# STORAGE.net
KiCad netlist of a schematic drawn in Altium Designer
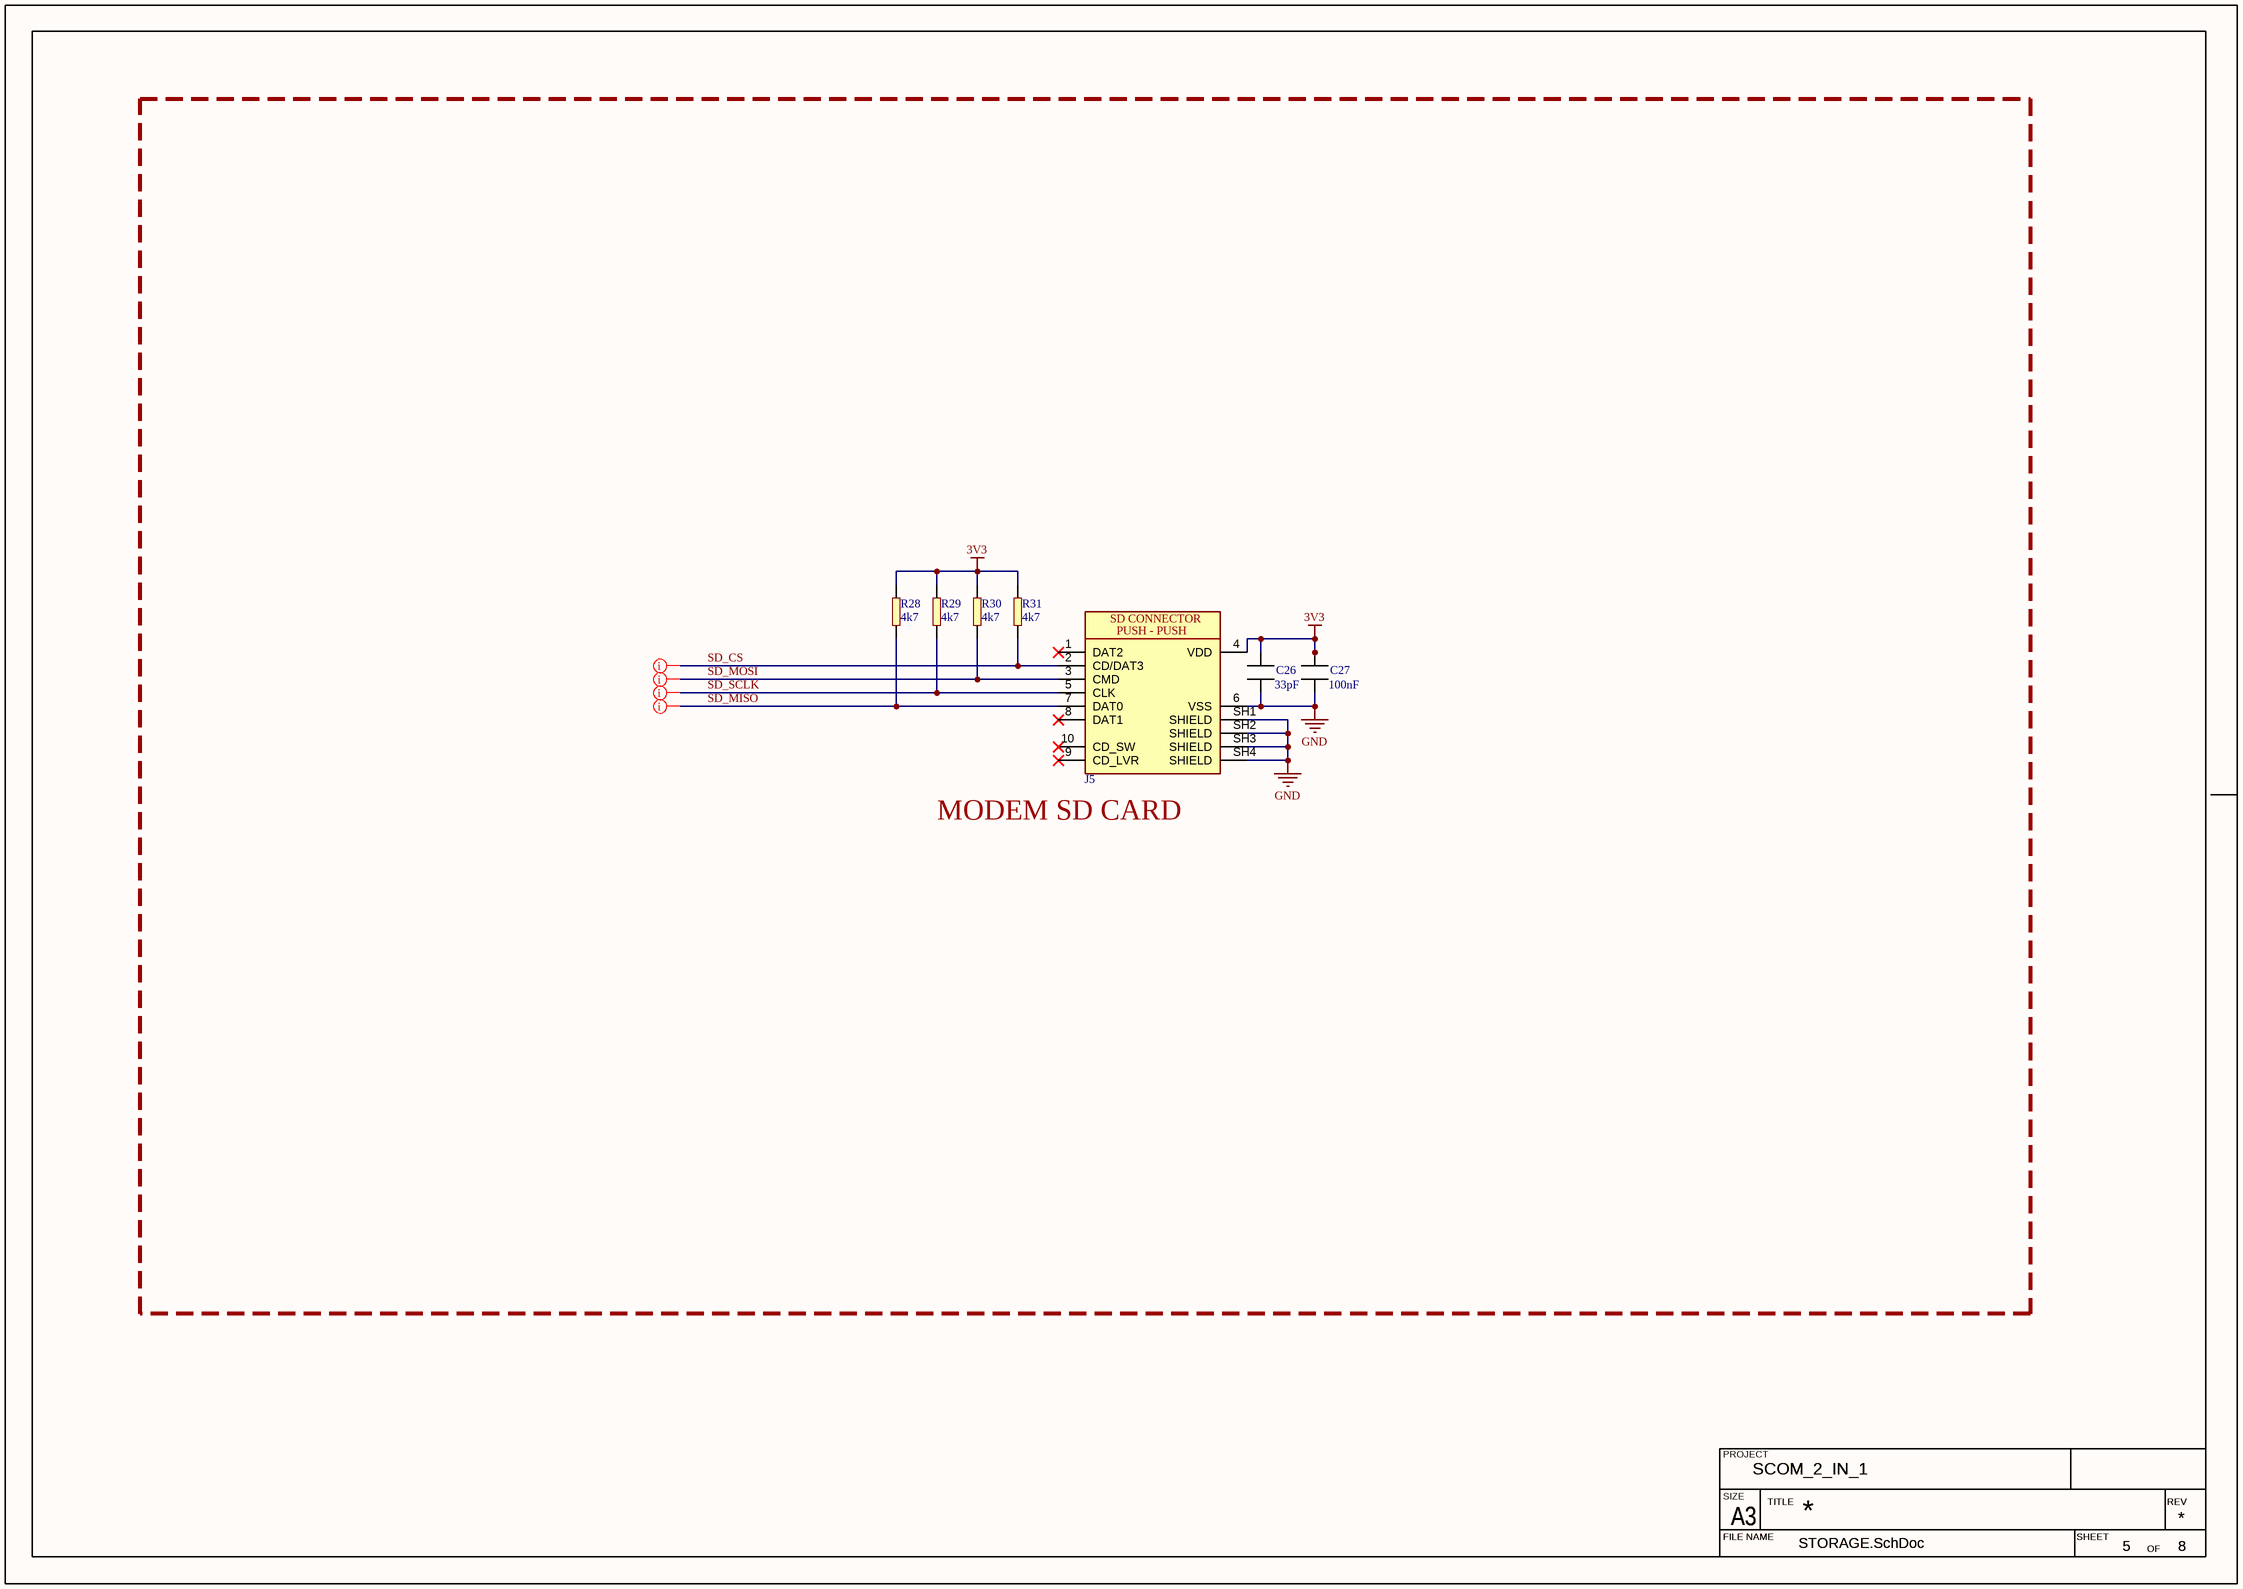
[diagram p0: STORAGE.SchDoc]

(export (version "E")
  (design (tool "Eeschema 10.0.6"))
  (components
    (comp (ref "C26")
      (value "33pF")
      (footprint "CAPC2012X13L")
      (description "Chip Capacitor, 2-Leads, Body 2.00x1.25mm, IPC High Density")
      (fields (field (name "Comment") "MLCC_0805"))
      (libsource (lib "Capacitor") (part "MLCC_0805"))
    )
    (comp (ref "C27")
      (value "100nF")
      (footprint "CAPC2012X13L")
      (description "Chip Capacitor, 2-Leads, Body 2.00x1.25mm, IPC High Density")
      (fields (field (name "Comment") "MLCC_0805"))
      (libsource (lib "Capacitor") (part "MLCC_0805"))
    )
    (comp (ref "J5")
      (value "5033981892")
      (footprint "5033981892")
      (description "9 (8 + 1) Position Card Connector Secure Digital - microSD™ Surface Mount, Right Angle Gold")
      (libsource (lib "Connectors") (part "5033981892"))
    )
    (comp (ref "R28")
      (value "4k7")
      (footprint "RES_0603")
      (description "RES_0603")
      (fields (field (name "Comment") "ERP_101-1"))
      (libsource (lib "Resistor") (part "RES_0603"))
    )
    (comp (ref "R29")
      (value "4k7")
      (footprint "RES_0603")
      (description "RES_0603")
      (fields (field (name "Comment") "ERP_101-1"))
      (libsource (lib "Resistor") (part "RES_0603"))
    )
    (comp (ref "R30")
      (value "4k7")
      (footprint "RES_0603")
      (description "RES_0603")
      (fields (field (name "Comment") "ERP_101-1"))
      (libsource (lib "Resistor") (part "RES_0603"))
    )
    (comp (ref "R31")
      (value "4k7")
      (footprint "RES_0603")
      (description "RES_0603")
      (fields (field (name "Comment") "ERP_101-1"))
      (libsource (lib "Resistor") (part "RES_0603"))
    )
  )
  (nets
    (net (code "1") (name "/SD_CS") (class "Default")
      (node (ref "J5") (pin "2") (pinfunction "CD/DAT3_2") (pintype "passive"))
      (node (ref "R31") (pin "1") (pinfunction "1_1") (pintype "passive"))
    )
    (net (code "2") (name "/SD_MISO") (class "Default")
      (node (ref "J5") (pin "7") (pinfunction "DAT0_7") (pintype "passive"))
      (node (ref "R28") (pin "1") (pinfunction "1_1") (pintype "passive"))
    )
    (net (code "3") (name "/SD_MOSI") (class "Default")
      (node (ref "J5") (pin "3") (pinfunction "CMD_3") (pintype "passive"))
      (node (ref "R30") (pin "1") (pinfunction "1_1") (pintype "passive"))
    )
    (net (code "4") (name "/SD_SCLK") (class "Default")
      (node (ref "J5") (pin "5") (pinfunction "CLK_5") (pintype "passive"))
      (node (ref "R29") (pin "1") (pinfunction "1_1") (pintype "passive"))
    )
    (net (code "5") (name "3V3") (class "Default")
      (node (ref "C26") (pin "1") (pinfunction "1_1") (pintype "passive"))
      (node (ref "C27") (pin "1") (pinfunction "1_1") (pintype "passive"))
      (node (ref "J5") (pin "4") (pinfunction "VDD_4") (pintype "passive"))
      (node (ref "R28") (pin "2") (pinfunction "2_2") (pintype "passive"))
      (node (ref "R29") (pin "2") (pinfunction "2_2") (pintype "passive"))
      (node (ref "R30") (pin "2") (pinfunction "2_2") (pintype "passive"))
      (node (ref "R31") (pin "2") (pinfunction "2_2") (pintype "passive"))
    )
    (net (code "6") (name "GND") (class "Default")
      (node (ref "C26") (pin "2") (pinfunction "2_2") (pintype "passive"))
      (node (ref "C27") (pin "2") (pinfunction "2_2") (pintype "passive"))
      (node (ref "J5") (pin "6") (pinfunction "VSS_6") (pintype "power_in"))
      (node (ref "J5") (pin "SH1") (pinfunction "SHIELD_SH1") (pintype "power_in"))
      (node (ref "J5") (pin "SH2") (pinfunction "SHIELD_SH2") (pintype "power_in"))
      (node (ref "J5") (pin "SH3") (pinfunction "SHIELD_SH3") (pintype "power_in"))
      (node (ref "J5") (pin "SH4") (pinfunction "SHIELD_SH4") (pintype "power_in"))
    )
    (net (code "7") (name "unconnected-(J5-CD_LVR-Pad9)") (class "Default")
      (node (ref "J5") (pin "9") (pinfunction "CD_LVR_9") (pintype "power_in+no_connect"))
    )
    (net (code "8") (name "unconnected-(J5-CD_SW-Pad10)") (class "Default")
      (node (ref "J5") (pin "10") (pinfunction "CD_SW_10") (pintype "passive+no_connect"))
    )
    (net (code "9") (name "unconnected-(J5-DAT1-Pad8)") (class "Default")
      (node (ref "J5") (pin "8") (pinfunction "DAT1_8") (pintype "passive+no_connect"))
    )
    (net (code "10") (name "unconnected-(J5-DAT2-Pad1)") (class "Default")
      (node (ref "J5") (pin "1") (pinfunction "DAT2_1") (pintype "passive+no_connect"))
    )
  )
)
